# servodengen1_1.net
KiCad netlist of a schematic drawn in EAGLE
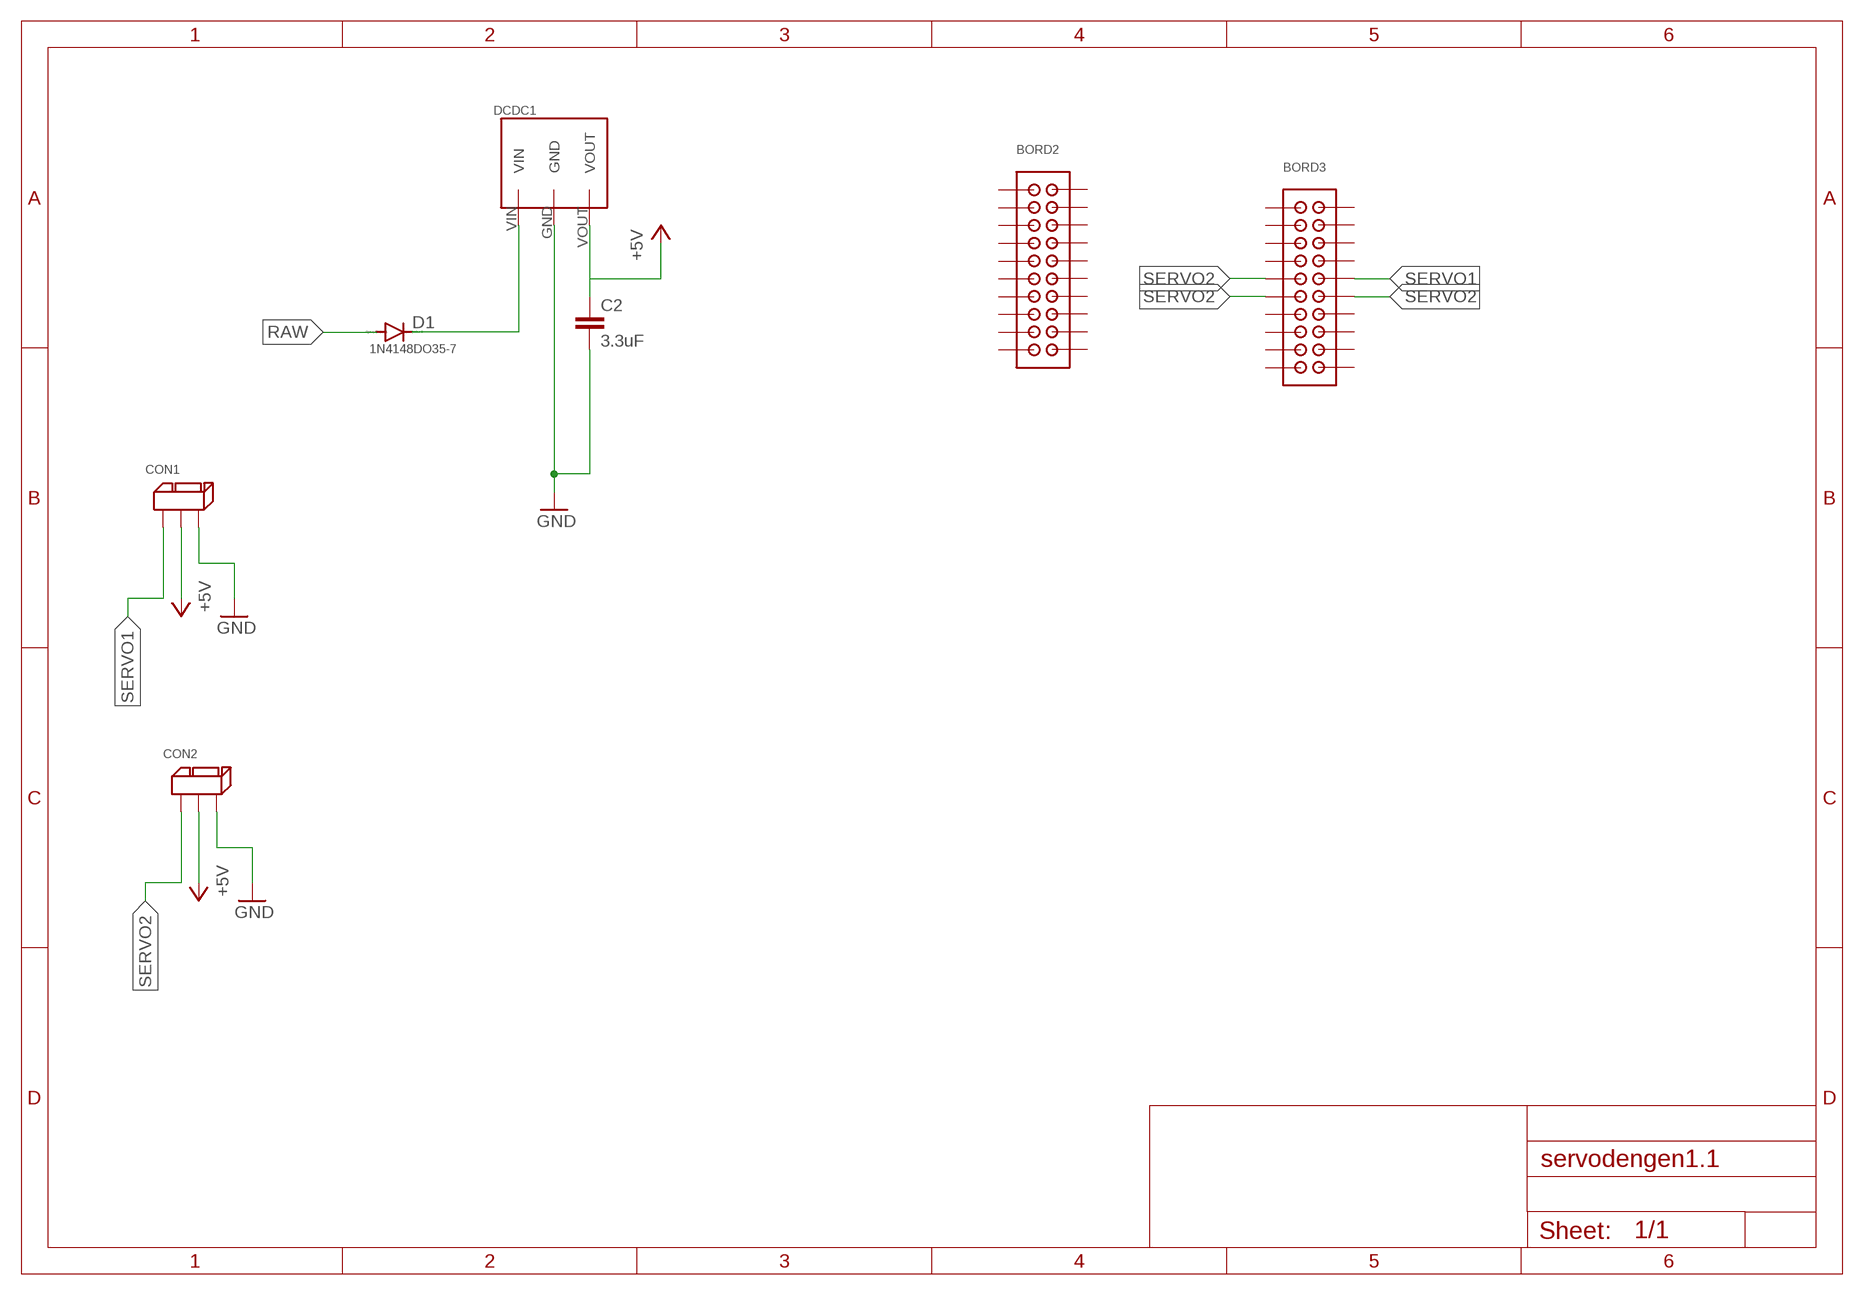
[diagram p0: schematic, sheet 1]

(export (version "E")
  (design (tool "Eeschema 10.0.6"))
  (components
    (comp (ref "BORD2")
      (value "2X10")
      (footprint "eagle-import:2X10")
      (libsource (lib "eagle-import") (part "2X10"))
    )
    (comp (ref "BORD3")
      (value "2X10")
      (footprint "eagle-import:2X10")
      (libsource (lib "eagle-import") (part "2X10"))
    )
    (comp (ref "C2")
      (value "3.3uF")
      (footprint "eagle-import:C025-024X044")
      (libsource (lib "eagle-import") (part "C-EU025-024X044"))
    )
    (comp (ref "CON1")
      (value "3PIN")
      (footprint "eagle-import:3PIN")
      (libsource (lib "eagle-import") (part "3PIN"))
    )
    (comp (ref "CON2")
      (value "3PIN")
      (footprint "eagle-import:3PIN")
      (libsource (lib "eagle-import") (part "3PIN"))
    )
    (comp (ref "D1")
      (value "1N4148DO35-7")
      (footprint "eagle-import:DO35-7")
      (libsource (lib "eagle-import") (part "1N4148DO35-7"))
    )
    (comp (ref "DCDC1")
      (value "5V1A_M78AR05-1")
      (footprint "eagle-import:5V1A_M78AR05-1")
      (libsource (lib "eagle-import") (part "5V1A_M78AR05-1"))
    )
  )
  (nets
    (net (code "1") (name "+5V") (class "Default")
      (node (ref "C2") (pin "1") (pinfunction "1_1") (pintype "passive"))
      (node (ref "CON1") (pin "P$2") (pinfunction "P$2_P$2") (pintype "bidirectional"))
      (node (ref "CON2") (pin "P$2") (pinfunction "P$2_P$2") (pintype "bidirectional"))
      (node (ref "DCDC1") (pin "VOUT") (pinfunction "VOUT_VOUT") (pintype "bidirectional"))
    )
    (net (code "2") (name "GND") (class "Default")
      (node (ref "C2") (pin "2") (pinfunction "2_2") (pintype "passive"))
      (node (ref "CON1") (pin "P$3") (pinfunction "P$3_P$3") (pintype "bidirectional"))
      (node (ref "CON2") (pin "P$3") (pinfunction "P$3_P$3") (pintype "bidirectional"))
      (node (ref "DCDC1") (pin "GND") (pinfunction "GND_GND") (pintype "bidirectional"))
    )
    (net (code "3") (name "RAW") (class "Default")
      (node (ref "D1") (pin "C") (pinfunction "C_C") (pintype "passive"))
      (node (ref "DCDC1") (pin "VIN") (pinfunction "VIN_VIN") (pintype "bidirectional"))
    )
    (net (code "4") (name "SERVO1") (class "Default")
      (node (ref "BORD3") (pin "P$10") (pinfunction "P$10_P$10") (pintype "bidirectional"))
      (node (ref "CON1") (pin "P$1") (pinfunction "P$1_P$1") (pintype "bidirectional"))
    )
    (net (code "5") (name "SERVO2") (class "Default")
      (node (ref "BORD3") (pin "P$11") (pinfunction "P$11_P$11") (pintype "bidirectional"))
      (node (ref "BORD3") (pin "P$12") (pinfunction "P$12_P$12") (pintype "bidirectional"))
      (node (ref "BORD3") (pin "P$9") (pinfunction "P$9_P$9") (pintype "bidirectional"))
      (node (ref "CON2") (pin "P$1") (pinfunction "P$1_P$1") (pintype "bidirectional"))
    )
    (net (code "6") (name "unconnected-(BORD2-PadP$1)") (class "Default")
      (node (ref "BORD2") (pin "P$1") (pinfunction "P$1_P$1") (pintype "bidirectional"))
    )
    (net (code "7") (name "unconnected-(BORD2-PadP$2)") (class "Default")
      (node (ref "BORD2") (pin "P$2") (pinfunction "P$2_P$2") (pintype "bidirectional"))
    )
    (net (code "8") (name "unconnected-(BORD2-PadP$3)") (class "Default")
      (node (ref "BORD2") (pin "P$3") (pinfunction "P$3_P$3") (pintype "bidirectional"))
    )
    (net (code "9") (name "unconnected-(BORD2-PadP$4)") (class "Default")
      (node (ref "BORD2") (pin "P$4") (pinfunction "P$4_P$4") (pintype "bidirectional"))
    )
    (net (code "10") (name "unconnected-(BORD2-PadP$5)") (class "Default")
      (node (ref "BORD2") (pin "P$5") (pinfunction "P$5_P$5") (pintype "bidirectional"))
    )
    (net (code "11") (name "unconnected-(BORD2-PadP$6)") (class "Default")
      (node (ref "BORD2") (pin "P$6") (pinfunction "P$6_P$6") (pintype "bidirectional"))
    )
    (net (code "12") (name "unconnected-(BORD2-PadP$7)") (class "Default")
      (node (ref "BORD2") (pin "P$7") (pinfunction "P$7_P$7") (pintype "bidirectional"))
    )
    (net (code "13") (name "unconnected-(BORD2-PadP$8)") (class "Default")
      (node (ref "BORD2") (pin "P$8") (pinfunction "P$8_P$8") (pintype "bidirectional"))
    )
    (net (code "14") (name "unconnected-(BORD2-PadP$9)") (class "Default")
      (node (ref "BORD2") (pin "P$9") (pinfunction "P$9_P$9") (pintype "bidirectional"))
    )
    (net (code "15") (name "unconnected-(BORD2-PadP$10)") (class "Default")
      (node (ref "BORD2") (pin "P$10") (pinfunction "P$10_P$10") (pintype "bidirectional"))
    )
    (net (code "16") (name "unconnected-(BORD2-PadP$11)") (class "Default")
      (node (ref "BORD2") (pin "P$11") (pinfunction "P$11_P$11") (pintype "bidirectional"))
    )
    (net (code "17") (name "unconnected-(BORD2-PadP$12)") (class "Default")
      (node (ref "BORD2") (pin "P$12") (pinfunction "P$12_P$12") (pintype "bidirectional"))
    )
    (net (code "18") (name "unconnected-(BORD2-PadP$13)") (class "Default")
      (node (ref "BORD2") (pin "P$13") (pinfunction "P$13_P$13") (pintype "bidirectional"))
    )
    (net (code "19") (name "unconnected-(BORD2-PadP$14)") (class "Default")
      (node (ref "BORD2") (pin "P$14") (pinfunction "P$14_P$14") (pintype "bidirectional"))
    )
    (net (code "20") (name "unconnected-(BORD2-PadP$15)") (class "Default")
      (node (ref "BORD2") (pin "P$15") (pinfunction "P$15_P$15") (pintype "bidirectional"))
    )
    (net (code "21") (name "unconnected-(BORD2-PadP$16)") (class "Default")
      (node (ref "BORD2") (pin "P$16") (pinfunction "P$16_P$16") (pintype "bidirectional"))
    )
    (net (code "22") (name "unconnected-(BORD2-PadP$17)") (class "Default")
      (node (ref "BORD2") (pin "P$17") (pinfunction "P$17_P$17") (pintype "bidirectional"))
    )
    (net (code "23") (name "unconnected-(BORD2-PadP$18)") (class "Default")
      (node (ref "BORD2") (pin "P$18") (pinfunction "P$18_P$18") (pintype "bidirectional"))
    )
    (net (code "24") (name "unconnected-(BORD2-PadP$19)") (class "Default")
      (node (ref "BORD2") (pin "P$19") (pinfunction "P$19_P$19") (pintype "bidirectional"))
    )
    (net (code "25") (name "unconnected-(BORD2-PadP$20)") (class "Default")
      (node (ref "BORD2") (pin "P$20") (pinfunction "P$20_P$20") (pintype "bidirectional"))
    )
    (net (code "26") (name "unconnected-(BORD3-PadP$1)") (class "Default")
      (node (ref "BORD3") (pin "P$1") (pinfunction "P$1_P$1") (pintype "bidirectional"))
    )
    (net (code "27") (name "unconnected-(BORD3-PadP$2)") (class "Default")
      (node (ref "BORD3") (pin "P$2") (pinfunction "P$2_P$2") (pintype "bidirectional"))
    )
    (net (code "28") (name "unconnected-(BORD3-PadP$3)") (class "Default")
      (node (ref "BORD3") (pin "P$3") (pinfunction "P$3_P$3") (pintype "bidirectional"))
    )
    (net (code "29") (name "unconnected-(BORD3-PadP$4)") (class "Default")
      (node (ref "BORD3") (pin "P$4") (pinfunction "P$4_P$4") (pintype "bidirectional"))
    )
    (net (code "30") (name "unconnected-(BORD3-PadP$5)") (class "Default")
      (node (ref "BORD3") (pin "P$5") (pinfunction "P$5_P$5") (pintype "bidirectional"))
    )
    (net (code "31") (name "unconnected-(BORD3-PadP$6)") (class "Default")
      (node (ref "BORD3") (pin "P$6") (pinfunction "P$6_P$6") (pintype "bidirectional"))
    )
    (net (code "32") (name "unconnected-(BORD3-PadP$7)") (class "Default")
      (node (ref "BORD3") (pin "P$7") (pinfunction "P$7_P$7") (pintype "bidirectional"))
    )
    (net (code "33") (name "unconnected-(BORD3-PadP$8)") (class "Default")
      (node (ref "BORD3") (pin "P$8") (pinfunction "P$8_P$8") (pintype "bidirectional"))
    )
    (net (code "34") (name "unconnected-(BORD3-PadP$13)") (class "Default")
      (node (ref "BORD3") (pin "P$13") (pinfunction "P$13_P$13") (pintype "bidirectional"))
    )
    (net (code "35") (name "unconnected-(BORD3-PadP$14)") (class "Default")
      (node (ref "BORD3") (pin "P$14") (pinfunction "P$14_P$14") (pintype "bidirectional"))
    )
    (net (code "36") (name "unconnected-(BORD3-PadP$15)") (class "Default")
      (node (ref "BORD3") (pin "P$15") (pinfunction "P$15_P$15") (pintype "bidirectional"))
    )
    (net (code "37") (name "unconnected-(BORD3-PadP$16)") (class "Default")
      (node (ref "BORD3") (pin "P$16") (pinfunction "P$16_P$16") (pintype "bidirectional"))
    )
    (net (code "38") (name "unconnected-(BORD3-PadP$17)") (class "Default")
      (node (ref "BORD3") (pin "P$17") (pinfunction "P$17_P$17") (pintype "bidirectional"))
    )
    (net (code "39") (name "unconnected-(BORD3-PadP$18)") (class "Default")
      (node (ref "BORD3") (pin "P$18") (pinfunction "P$18_P$18") (pintype "bidirectional"))
    )
    (net (code "40") (name "unconnected-(BORD3-PadP$19)") (class "Default")
      (node (ref "BORD3") (pin "P$19") (pinfunction "P$19_P$19") (pintype "bidirectional"))
    )
    (net (code "41") (name "unconnected-(BORD3-PadP$20)") (class "Default")
      (node (ref "BORD3") (pin "P$20") (pinfunction "P$20_P$20") (pintype "bidirectional"))
    )
    (net (code "42") (name "unconnected-(D1-PadA)") (class "Default")
      (node (ref "D1") (pin "A") (pinfunction "A_A") (pintype "passive"))
    )
  )
)
